# PiButtons7.net
KiCad netlist of a schematic drawn in EAGLE
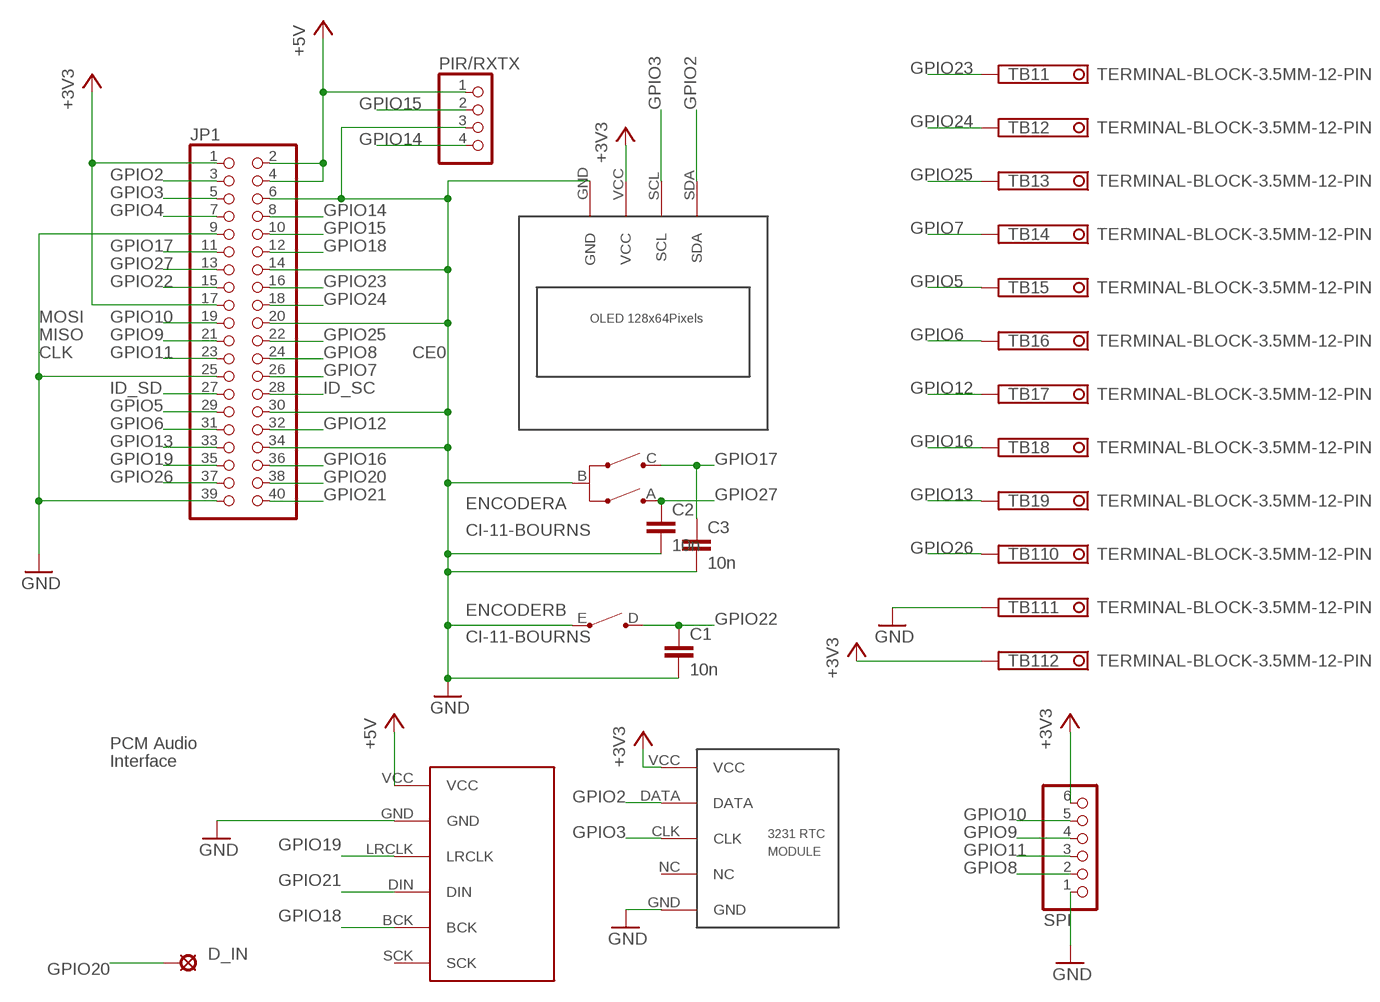
[diagram p0: schematic, sheet 1]

(export (version "E")
  (design (tool "Eeschema 10.0.6"))
  (components
    (comp (ref "C1")
      (value "10n")
      (footprint "eagle-import:C050-025X075")
      (libsource (lib "eagle-import") (part "C-EU050-025X075"))
    )
    (comp (ref "C2")
      (value "10n")
      (footprint "eagle-import:C050-025X075")
      (libsource (lib "eagle-import") (part "C-EU050-025X075"))
    )
    (comp (ref "C3")
      (value "10n")
      (footprint "eagle-import:C050-025X075")
      (libsource (lib "eagle-import") (part "C-EU050-025X075"))
    )
    (comp (ref "D_IN")
      (value "LSP10")
      (footprint "eagle-import:LSP10")
      (libsource (lib "eagle-import") (part "LSP10"))
    )
    (comp (ref "ENCODER")
      (value "CI-11-BOURNS")
      (footprint "eagle-import:CI-11")
      (libsource (lib "eagle-import") (part "CI-11BOURNS"))
    )
    (comp (ref "JP1")
      (value "PINHD-2X20")
      (footprint "eagle-import:2X20")
      (libsource (lib "eagle-import") (part "PINHD-2X20"))
    )
    (comp (ref "PIR/RXTX")
      (value "PINHD-1X4")
      (footprint "eagle-import:1X04")
      (libsource (lib "eagle-import") (part "PINHD-1X4"))
    )
    (comp (ref "SPI")
      (value "PINHD-1X6")
      (footprint "eagle-import:1X06")
      (libsource (lib "eagle-import") (part "PINHD-1X6"))
    )
    (comp (ref "TB1")
      (value "TERMINAL-BLOCK-3.5MM-12-PIN")
      (footprint "eagle-import:TERMINAL-BLOCK-12-PIN-3.5MM-LONG-PAD")
      (libsource (lib "eagle-import") (part "TERMINAL-BLOCK-3.5MM-12-PIN"))
    )
    (comp (ref "U$1")
      (value "PCM5102CARDPCB")
      (footprint "eagle-import:PCM5102CARD")
      (libsource (lib "eagle-import") (part "PCM5102CARDPCB"))
    )
    (comp (ref "U$2")
      (value "OLEDI2CDISPLAY")
      (footprint "eagle-import:OLEDI2C")
      (libsource (lib "eagle-import") (part "OLEDI2CDISPLAY"))
    )
    (comp (ref "U$3")
      (value "RTC3231PCB")
      (footprint "eagle-import:RTC3231PCB")
      (libsource (lib "eagle-import") (part "RTC3231PCB"))
    )
  )
  (nets
    (net (code "1") (name "+3V3") (class "Default")
      (node (ref "JP1") (pin "1") (pinfunction "1_1") (pintype "passive"))
      (node (ref "JP1") (pin "17") (pinfunction "17_17") (pintype "passive"))
      (node (ref "SPI") (pin "6") (pinfunction "6_6") (pintype "passive"))
      (node (ref "TB1") (pin "12") (pinfunction "K_12") (pintype "passive"))
      (node (ref "U$2") (pin "VCC") (pinfunction "VCC_VCC") (pintype "bidirectional"))
      (node (ref "U$3") (pin "VCC") (pinfunction "VCC_VCC") (pintype "bidirectional"))
    )
    (net (code "2") (name "+5V") (class "Default")
      (node (ref "JP1") (pin "2") (pinfunction "2_2") (pintype "passive"))
      (node (ref "JP1") (pin "4") (pinfunction "4_4") (pintype "passive"))
      (node (ref "PIR/RXTX") (pin "1") (pinfunction "1_1") (pintype "passive"))
      (node (ref "U$1") (pin "VCC") (pinfunction "VCC_VCC") (pintype "bidirectional"))
    )
    (net (code "3") (name "/GPIO2") (class "Default")
      (node (ref "JP1") (pin "3") (pinfunction "3_3") (pintype "passive"))
      (node (ref "U$2") (pin "SDA") (pinfunction "SDA_SDA") (pintype "bidirectional"))
      (node (ref "U$3") (pin "DATA") (pinfunction "DATA_DATA") (pintype "bidirectional"))
    )
    (net (code "4") (name "/GPIO3") (class "Default")
      (node (ref "JP1") (pin "5") (pinfunction "5_5") (pintype "passive"))
      (node (ref "U$2") (pin "SCL") (pinfunction "SCL_SCL") (pintype "bidirectional"))
      (node (ref "U$3") (pin "CLK") (pinfunction "CLK_CLK") (pintype "bidirectional"))
    )
    (net (code "5") (name "/GPIO4") (class "Default")
      (node (ref "JP1") (pin "7") (pinfunction "7_7") (pintype "passive"))
    )
    (net (code "6") (name "/GPIO5") (class "Default")
      (node (ref "JP1") (pin "29") (pinfunction "29_29") (pintype "passive"))
      (node (ref "TB1") (pin "5") (pinfunction "K_5") (pintype "passive"))
    )
    (net (code "7") (name "/GPIO6") (class "Default")
      (node (ref "JP1") (pin "31") (pinfunction "31_31") (pintype "passive"))
      (node (ref "TB1") (pin "6") (pinfunction "K_6") (pintype "passive"))
    )
    (net (code "8") (name "/GPIO7") (class "Default")
      (node (ref "JP1") (pin "26") (pinfunction "26_26") (pintype "passive"))
      (node (ref "TB1") (pin "4") (pinfunction "K_4") (pintype "passive"))
    )
    (net (code "9") (name "/GPIO8") (class "Default")
      (node (ref "JP1") (pin "24") (pinfunction "24_24") (pintype "passive"))
      (node (ref "SPI") (pin "2") (pinfunction "2_2") (pintype "passive"))
    )
    (net (code "10") (name "/GPIO9") (class "Default")
      (node (ref "JP1") (pin "21") (pinfunction "21_21") (pintype "passive"))
      (node (ref "SPI") (pin "4") (pinfunction "4_4") (pintype "passive"))
    )
    (net (code "11") (name "/GPIO10") (class "Default")
      (node (ref "JP1") (pin "19") (pinfunction "19_19") (pintype "passive"))
      (node (ref "SPI") (pin "5") (pinfunction "5_5") (pintype "passive"))
    )
    (net (code "12") (name "/GPIO11") (class "Default")
      (node (ref "JP1") (pin "23") (pinfunction "23_23") (pintype "passive"))
      (node (ref "SPI") (pin "3") (pinfunction "3_3") (pintype "passive"))
    )
    (net (code "13") (name "/GPIO12") (class "Default")
      (node (ref "JP1") (pin "32") (pinfunction "32_32") (pintype "passive"))
      (node (ref "TB1") (pin "7") (pinfunction "K_7") (pintype "passive"))
    )
    (net (code "14") (name "/GPIO13") (class "Default")
      (node (ref "JP1") (pin "33") (pinfunction "33_33") (pintype "passive"))
      (node (ref "TB1") (pin "9") (pinfunction "K_9") (pintype "passive"))
    )
    (net (code "15") (name "/GPIO14") (class "Default")
      (node (ref "JP1") (pin "8") (pinfunction "8_8") (pintype "passive"))
      (node (ref "PIR/RXTX") (pin "4") (pinfunction "4_4") (pintype "passive"))
    )
    (net (code "16") (name "/GPIO15") (class "Default")
      (node (ref "JP1") (pin "10") (pinfunction "10_10") (pintype "passive"))
      (node (ref "PIR/RXTX") (pin "2") (pinfunction "2_2") (pintype "passive"))
    )
    (net (code "17") (name "/GPIO16") (class "Default")
      (node (ref "JP1") (pin "36") (pinfunction "36_36") (pintype "passive"))
      (node (ref "TB1") (pin "8") (pinfunction "K_8") (pintype "passive"))
    )
    (net (code "18") (name "/GPIO17") (class "Default")
      (node (ref "C3") (pin "1") (pinfunction "1_1") (pintype "passive"))
      (node (ref "ENCODER") (pin "C") (pinfunction "B_C") (pintype "passive"))
      (node (ref "JP1") (pin "11") (pinfunction "11_11") (pintype "passive"))
    )
    (net (code "19") (name "/GPIO18") (class "Default")
      (node (ref "JP1") (pin "12") (pinfunction "12_12") (pintype "passive"))
      (node (ref "U$1") (pin "BCK") (pinfunction "BCK_BCK") (pintype "bidirectional"))
    )
    (net (code "20") (name "/GPIO19") (class "Default")
      (node (ref "JP1") (pin "35") (pinfunction "35_35") (pintype "passive"))
      (node (ref "U$1") (pin "LRCLK") (pinfunction "LRCLK_LRCLK") (pintype "bidirectional"))
    )
    (net (code "21") (name "/GPIO20") (class "Default")
      (node (ref "D_IN") (pin "MP") (pinfunction "MP_MP") (pintype "passive"))
      (node (ref "JP1") (pin "38") (pinfunction "38_38") (pintype "passive"))
    )
    (net (code "22") (name "/GPIO21") (class "Default")
      (node (ref "JP1") (pin "40") (pinfunction "40_40") (pintype "passive"))
      (node (ref "U$1") (pin "DIN") (pinfunction "DIN_DIN") (pintype "bidirectional"))
    )
    (net (code "23") (name "/GPIO22") (class "Default")
      (node (ref "C1") (pin "1") (pinfunction "1_1") (pintype "passive"))
      (node (ref "ENCODER") (pin "D") (pinfunction "D_D") (pintype "passive"))
      (node (ref "JP1") (pin "15") (pinfunction "15_15") (pintype "passive"))
    )
    (net (code "24") (name "/GPIO23") (class "Default")
      (node (ref "JP1") (pin "16") (pinfunction "16_16") (pintype "passive"))
      (node (ref "TB1") (pin "1") (pinfunction "K_1") (pintype "passive"))
    )
    (net (code "25") (name "/GPIO24") (class "Default")
      (node (ref "JP1") (pin "18") (pinfunction "18_18") (pintype "passive"))
      (node (ref "TB1") (pin "2") (pinfunction "K_2") (pintype "passive"))
    )
    (net (code "26") (name "/GPIO25") (class "Default")
      (node (ref "JP1") (pin "22") (pinfunction "22_22") (pintype "passive"))
      (node (ref "TB1") (pin "3") (pinfunction "K_3") (pintype "passive"))
    )
    (net (code "27") (name "/GPIO26") (class "Default")
      (node (ref "JP1") (pin "37") (pinfunction "37_37") (pintype "passive"))
      (node (ref "TB1") (pin "10") (pinfunction "K_10") (pintype "passive"))
    )
    (net (code "28") (name "/GPIO27") (class "Default")
      (node (ref "C2") (pin "1") (pinfunction "1_1") (pintype "passive"))
      (node (ref "ENCODER") (pin "A") (pinfunction "A_A") (pintype "passive"))
      (node (ref "JP1") (pin "13") (pinfunction "13_13") (pintype "passive"))
    )
    (net (code "29") (name "/ID_SC") (class "Default")
      (node (ref "JP1") (pin "28") (pinfunction "28_28") (pintype "passive"))
    )
    (net (code "30") (name "/ID_SD") (class "Default")
      (node (ref "JP1") (pin "27") (pinfunction "27_27") (pintype "passive"))
    )
    (net (code "31") (name "GND") (class "Default")
      (node (ref "C1") (pin "2") (pinfunction "2_2") (pintype "passive"))
      (node (ref "C2") (pin "2") (pinfunction "2_2") (pintype "passive"))
      (node (ref "C3") (pin "2") (pinfunction "2_2") (pintype "passive"))
      (node (ref "ENCODER") (pin "B") (pinfunction "C_B") (pintype "passive"))
      (node (ref "ENCODER") (pin "E") (pinfunction "E_E") (pintype "passive"))
      (node (ref "JP1") (pin "14") (pinfunction "14_14") (pintype "passive"))
      (node (ref "JP1") (pin "20") (pinfunction "20_20") (pintype "passive"))
      (node (ref "JP1") (pin "25") (pinfunction "25_25") (pintype "passive"))
      (node (ref "JP1") (pin "30") (pinfunction "30_30") (pintype "passive"))
      (node (ref "JP1") (pin "34") (pinfunction "34_34") (pintype "passive"))
      (node (ref "JP1") (pin "39") (pinfunction "39_39") (pintype "passive"))
      (node (ref "JP1") (pin "6") (pinfunction "6_6") (pintype "passive"))
      (node (ref "JP1") (pin "9") (pinfunction "9_9") (pintype "passive"))
      (node (ref "PIR/RXTX") (pin "3") (pinfunction "3_3") (pintype "passive"))
      (node (ref "SPI") (pin "1") (pinfunction "1_1") (pintype "passive"))
      (node (ref "TB1") (pin "11") (pinfunction "K_11") (pintype "passive"))
      (node (ref "U$1") (pin "GND") (pinfunction "GND_GND") (pintype "bidirectional"))
      (node (ref "U$2") (pin "GND") (pinfunction "GND_GND") (pintype "bidirectional"))
      (node (ref "U$3") (pin "GND") (pinfunction "GND_GND") (pintype "bidirectional"))
    )
    (net (code "32") (name "unconnected-(U$1-PadSCK)") (class "Default")
      (node (ref "U$1") (pin "SCK") (pinfunction "SCK_SCK") (pintype "bidirectional"))
    )
    (net (code "33") (name "unconnected-(U$3-PadNC)") (class "Default")
      (node (ref "U$3") (pin "NC") (pinfunction "NC_NC") (pintype "bidirectional"))
    )
  )
)
